# rcmix_v1.net
KiCad netlist of a schematic drawn in EAGLE
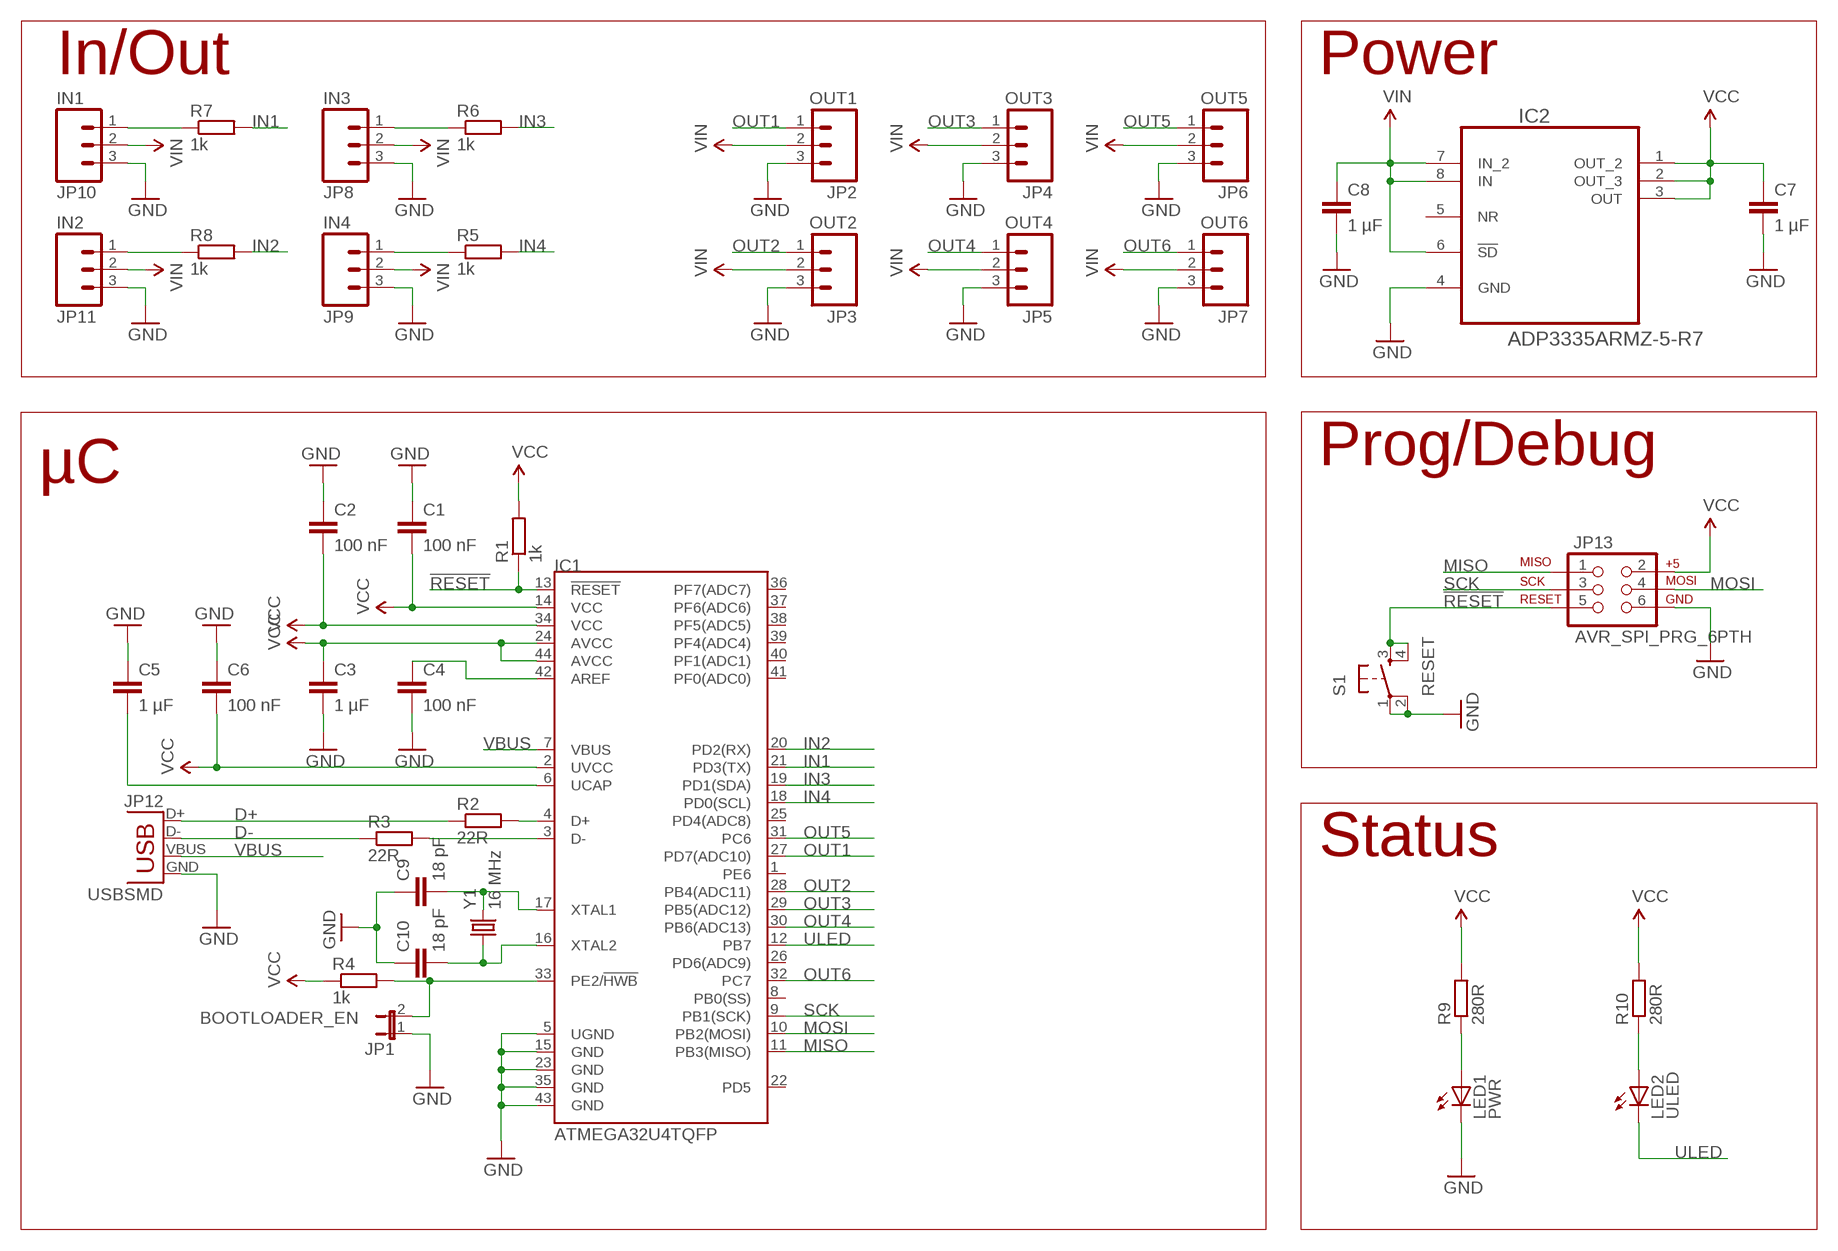
[diagram p0: schematic, sheet 1]

(export (version "E")
  (design (tool "Eeschema 10.0.6"))
  (components
    (comp (ref "C1")
      (value "100 nF")
      (footprint "eagle-import:C0603K")
      (libsource (lib "eagle-import") (part "C-EUC0603K"))
    )
    (comp (ref "C2")
      (value "100 nF")
      (footprint "eagle-import:C0603K")
      (libsource (lib "eagle-import") (part "C-EUC0603K"))
    )
    (comp (ref "C3")
      (value "1 µF")
      (footprint "eagle-import:C0603K")
      (libsource (lib "eagle-import") (part "C-EUC0603K"))
    )
    (comp (ref "C4")
      (value "100 nF")
      (footprint "eagle-import:C0603K")
      (libsource (lib "eagle-import") (part "C-EUC0603K"))
    )
    (comp (ref "C5")
      (value "1 µF")
      (footprint "eagle-import:C0603K")
      (libsource (lib "eagle-import") (part "C-EUC0603K"))
    )
    (comp (ref "C6")
      (value "100 nF")
      (footprint "eagle-import:C0603K")
      (libsource (lib "eagle-import") (part "C-EUC0603K"))
    )
    (comp (ref "C7")
      (value "1 µF")
      (footprint "eagle-import:C0603K")
      (libsource (lib "eagle-import") (part "C-EUC0603K"))
    )
    (comp (ref "C8")
      (value "1 µF")
      (footprint "eagle-import:C0603K")
      (libsource (lib "eagle-import") (part "C-EUC0603K"))
    )
    (comp (ref "C9")
      (value "18 pF")
      (footprint "eagle-import:C0603K")
      (libsource (lib "eagle-import") (part "C-EUC0603K"))
    )
    (comp (ref "C10")
      (value "18 pF")
      (footprint "eagle-import:C0603K")
      (libsource (lib "eagle-import") (part "C-EUC0603K"))
    )
    (comp (ref "IC1")
      (value "ATMEGA32U4TQFP")
      (footprint "eagle-import:SPARKFUN-DIGITALIC_TQFP44")
      (libsource (lib "eagle-import") (part "ATMEGA32U4TQFP"))
    )
    (comp (ref "IC2")
      (value "ADP3335ARMZ-5-R7")
      (footprint "eagle-import:SOP65P490X110-8N")
      (libsource (lib "eagle-import") (part "ADP3335ARMZ-5-R7"))
    )
    (comp (ref "JP1")
      (value "BOOTLOADER_EN")
      (footprint "eagle-import:JP1")
      (libsource (lib "eagle-import") (part "JP1E"))
    )
    (comp (ref "JP2")
      (value "OUT1")
      (footprint "eagle-import:1X03")
      (libsource (lib "eagle-import") (part "M03PTH"))
    )
    (comp (ref "JP3")
      (value "OUT2")
      (footprint "eagle-import:1X03")
      (libsource (lib "eagle-import") (part "M03PTH"))
    )
    (comp (ref "JP4")
      (value "OUT3")
      (footprint "eagle-import:1X03")
      (libsource (lib "eagle-import") (part "M03PTH"))
    )
    (comp (ref "JP5")
      (value "OUT4")
      (footprint "eagle-import:1X03")
      (libsource (lib "eagle-import") (part "M03PTH"))
    )
    (comp (ref "JP6")
      (value "OUT5")
      (footprint "eagle-import:1X03")
      (libsource (lib "eagle-import") (part "M03PTH"))
    )
    (comp (ref "JP7")
      (value "OUT6")
      (footprint "eagle-import:1X03")
      (libsource (lib "eagle-import") (part "M03PTH"))
    )
    (comp (ref "JP8")
      (value "IN3")
      (footprint "eagle-import:1X03")
      (libsource (lib "eagle-import") (part "M03PTH"))
    )
    (comp (ref "JP9")
      (value "IN4")
      (footprint "eagle-import:1X03")
      (libsource (lib "eagle-import") (part "M03PTH"))
    )
    (comp (ref "JP10")
      (value "IN1")
      (footprint "eagle-import:1X03")
      (libsource (lib "eagle-import") (part "M03PTH"))
    )
    (comp (ref "JP11")
      (value "IN2")
      (footprint "eagle-import:1X03")
      (libsource (lib "eagle-import") (part "M03PTH"))
    )
    (comp (ref "JP12")
      (value "USBSMD")
      (footprint "eagle-import:USB-MINIB")
      (libsource (lib "eagle-import") (part "USBSMD"))
    )
    (comp (ref "JP13")
      (value "AVR_SPI_PRG_6PTH")
      (footprint "eagle-import:2X3")
      (libsource (lib "eagle-import") (part "AVR_SPI_PRG_6PTH"))
    )
    (comp (ref "LED1")
      (value "PWR")
      (footprint "eagle-import:CHIP-LED0603")
      (libsource (lib "eagle-import") (part "LEDCHIP-LED0603"))
    )
    (comp (ref "LED2")
      (value "ULED")
      (footprint "eagle-import:CHIP-LED0603")
      (libsource (lib "eagle-import") (part "LEDCHIP-LED0603"))
    )
    (comp (ref "R1")
      (value "1k")
      (footprint "eagle-import:R0603")
      (libsource (lib "eagle-import") (part "R-EU_R0603"))
    )
    (comp (ref "R2")
      (value "22R")
      (footprint "eagle-import:R0603")
      (libsource (lib "eagle-import") (part "R-EU_R0603"))
    )
    (comp (ref "R3")
      (value "22R")
      (footprint "eagle-import:R0603")
      (libsource (lib "eagle-import") (part "R-EU_R0603"))
    )
    (comp (ref "R4")
      (value "1k")
      (footprint "eagle-import:R0603")
      (libsource (lib "eagle-import") (part "R-EU_R0603"))
    )
    (comp (ref "R5")
      (value "1k")
      (footprint "eagle-import:R0603")
      (libsource (lib "eagle-import") (part "R-EU_R0603"))
    )
    (comp (ref "R6")
      (value "1k")
      (footprint "eagle-import:R0603")
      (libsource (lib "eagle-import") (part "R-EU_R0603"))
    )
    (comp (ref "R7")
      (value "1k")
      (footprint "eagle-import:R0603")
      (libsource (lib "eagle-import") (part "R-EU_R0603"))
    )
    (comp (ref "R8")
      (value "1k")
      (footprint "eagle-import:R0603")
      (libsource (lib "eagle-import") (part "R-EU_R0603"))
    )
    (comp (ref "R9")
      (value "280R")
      (footprint "eagle-import:R0603")
      (libsource (lib "eagle-import") (part "R-EU_R0603"))
    )
    (comp (ref "R10")
      (value "280R")
      (footprint "eagle-import:R0603")
      (libsource (lib "eagle-import") (part "R-EU_R0603"))
    )
    (comp (ref "S1")
      (value "RESET")
      (footprint "eagle-import:TACTILE-PTH")
      (libsource (lib "eagle-import") (part "TAC_SWITCHPTH"))
    )
    (comp (ref "Y1")
      (value "16 MHz")
      (footprint "eagle-import:CRYSTAL-TXC-7A")
      (libsource (lib "eagle-import") (part "CRYSTALTXC-7A"))
    )
  )
  (nets
    (net (code "1") (name "/D+") (class "Default")
      (node (ref "JP12") (pin "D+") (pinfunction "D+_D+") (pintype "bidirectional"))
      (node (ref "R2") (pin "1") (pinfunction "1_1") (pintype "passive"))
    )
    (net (code "2") (name "/D-") (class "Default")
      (node (ref "JP12") (pin "D-") (pinfunction "D-_D-") (pintype "bidirectional"))
      (node (ref "R3") (pin "1") (pinfunction "1_1") (pintype "passive"))
    )
    (net (code "3") (name "/IN1") (class "Default")
      (node (ref "IC1") (pin "21") (pinfunction "PD3(TX)_21") (pintype "bidirectional"))
      (node (ref "R7") (pin "2") (pinfunction "2_2") (pintype "passive"))
    )
    (net (code "4") (name "/IN2") (class "Default")
      (node (ref "IC1") (pin "20") (pinfunction "PD2(RX)_20") (pintype "bidirectional"))
      (node (ref "R8") (pin "2") (pinfunction "2_2") (pintype "passive"))
    )
    (net (code "5") (name "/IN3") (class "Default")
      (node (ref "IC1") (pin "19") (pinfunction "PD1(SDA)_19") (pintype "bidirectional"))
      (node (ref "R6") (pin "2") (pinfunction "2_2") (pintype "passive"))
    )
    (net (code "6") (name "/IN4") (class "Default")
      (node (ref "IC1") (pin "18") (pinfunction "PD0(SCL)_18") (pintype "bidirectional"))
      (node (ref "R5") (pin "2") (pinfunction "2_2") (pintype "passive"))
    )
    (net (code "7") (name "/MISO") (class "Default")
      (node (ref "IC1") (pin "11") (pinfunction "PB3(MISO)_11") (pintype "bidirectional"))
      (node (ref "JP13") (pin "1") (pinfunction "1_1") (pintype "passive"))
    )
    (net (code "8") (name "/MOSI") (class "Default")
      (node (ref "IC1") (pin "10") (pinfunction "PB2(MOSI)_10") (pintype "bidirectional"))
      (node (ref "JP13") (pin "4") (pinfunction "4_4") (pintype "passive"))
    )
    (net (code "9") (name "/OUT1") (class "Default")
      (node (ref "IC1") (pin "27") (pinfunction "PD7(ADC10)_27") (pintype "bidirectional"))
      (node (ref "JP2") (pin "1") (pinfunction "1_1") (pintype "passive"))
    )
    (net (code "10") (name "/OUT2") (class "Default")
      (node (ref "IC1") (pin "28") (pinfunction "PB4(ADC11)_28") (pintype "bidirectional"))
      (node (ref "JP3") (pin "1") (pinfunction "1_1") (pintype "passive"))
    )
    (net (code "11") (name "/OUT3") (class "Default")
      (node (ref "IC1") (pin "29") (pinfunction "PB5(ADC12)_29") (pintype "bidirectional"))
      (node (ref "JP4") (pin "1") (pinfunction "1_1") (pintype "passive"))
    )
    (net (code "12") (name "/OUT4") (class "Default")
      (node (ref "IC1") (pin "30") (pinfunction "PB6(ADC13)_30") (pintype "bidirectional"))
      (node (ref "JP5") (pin "1") (pinfunction "1_1") (pintype "passive"))
    )
    (net (code "13") (name "/OUT5") (class "Default")
      (node (ref "IC1") (pin "31") (pinfunction "PC6_31") (pintype "bidirectional"))
      (node (ref "JP6") (pin "1") (pinfunction "1_1") (pintype "passive"))
    )
    (net (code "14") (name "/OUT6") (class "Default")
      (node (ref "IC1") (pin "32") (pinfunction "PC7_32") (pintype "bidirectional"))
      (node (ref "JP7") (pin "1") (pinfunction "1_1") (pintype "passive"))
    )
    (net (code "15") (name "/SCK") (class "Default")
      (node (ref "IC1") (pin "9") (pinfunction "PB1(SCK)_9") (pintype "bidirectional"))
      (node (ref "JP13") (pin "3") (pinfunction "3_3") (pintype "passive"))
    )
    (net (code "16") (name "/ULED") (class "Default")
      (node (ref "IC1") (pin "12") (pinfunction "PB7_12") (pintype "bidirectional"))
      (node (ref "LED2") (pin "C") (pinfunction "C_C") (pintype "passive"))
    )
    (net (code "17") (name "/VBUS") (class "Default")
      (node (ref "IC1") (pin "7") (pinfunction "VBUS_7") (pintype "bidirectional"))
      (node (ref "JP12") (pin "VBUS") (pinfunction "VBUS_VBUS") (pintype "bidirectional"))
    )
    (net (code "18") (name "/~{RESET}") (class "Default")
      (node (ref "IC1") (pin "13") (pinfunction "~{RESET}_13") (pintype "bidirectional"))
      (node (ref "JP13") (pin "5") (pinfunction "5_5") (pintype "passive"))
      (node (ref "R1") (pin "1") (pinfunction "1_1") (pintype "passive"))
      (node (ref "S1") (pin "3") (pinfunction "3_3") (pintype "passive"))
      (node (ref "S1") (pin "4") (pinfunction "4_4") (pintype "passive"))
    )
    (net (code "19") (name "GND") (class "Default")
      (node (ref "C1") (pin "1") (pinfunction "1_1") (pintype "passive"))
      (node (ref "C10") (pin "1") (pinfunction "1_1") (pintype "passive"))
      (node (ref "C2") (pin "1") (pinfunction "1_1") (pintype "passive"))
      (node (ref "C3") (pin "2") (pinfunction "2_2") (pintype "passive"))
      (node (ref "C4") (pin "2") (pinfunction "2_2") (pintype "passive"))
      (node (ref "C5") (pin "1") (pinfunction "1_1") (pintype "passive"))
      (node (ref "C6") (pin "1") (pinfunction "1_1") (pintype "passive"))
      (node (ref "C7") (pin "2") (pinfunction "2_2") (pintype "passive"))
      (node (ref "C8") (pin "2") (pinfunction "2_2") (pintype "passive"))
      (node (ref "C9") (pin "1") (pinfunction "1_1") (pintype "passive"))
      (node (ref "IC1") (pin "15") (pinfunction "GND_15") (pintype "bidirectional"))
      (node (ref "IC1") (pin "23") (pinfunction "GND_23") (pintype "bidirectional"))
      (node (ref "IC1") (pin "35") (pinfunction "GND_35") (pintype "bidirectional"))
      (node (ref "IC1") (pin "43") (pinfunction "GND_43") (pintype "bidirectional"))
      (node (ref "IC1") (pin "5") (pinfunction "UGND_5") (pintype "bidirectional"))
      (node (ref "IC2") (pin "4") (pinfunction "GND_4") (pintype "passive"))
      (node (ref "JP1") (pin "1") (pinfunction "1_1") (pintype "passive"))
      (node (ref "JP10") (pin "3") (pinfunction "3_3") (pintype "passive"))
      (node (ref "JP11") (pin "3") (pinfunction "3_3") (pintype "passive"))
      (node (ref "JP12") (pin "GND") (pinfunction "GND_GND") (pintype "bidirectional"))
      (node (ref "JP13") (pin "6") (pinfunction "6_6") (pintype "passive"))
      (node (ref "JP2") (pin "3") (pinfunction "3_3") (pintype "passive"))
      (node (ref "JP3") (pin "3") (pinfunction "3_3") (pintype "passive"))
      (node (ref "JP4") (pin "3") (pinfunction "3_3") (pintype "passive"))
      (node (ref "JP5") (pin "3") (pinfunction "3_3") (pintype "passive"))
      (node (ref "JP6") (pin "3") (pinfunction "3_3") (pintype "passive"))
      (node (ref "JP7") (pin "3") (pinfunction "3_3") (pintype "passive"))
      (node (ref "JP8") (pin "3") (pinfunction "3_3") (pintype "passive"))
      (node (ref "JP9") (pin "3") (pinfunction "3_3") (pintype "passive"))
      (node (ref "LED1") (pin "C") (pinfunction "C_C") (pintype "passive"))
      (node (ref "S1") (pin "1") (pinfunction "1_1") (pintype "passive"))
      (node (ref "S1") (pin "2") (pinfunction "2_2") (pintype "passive"))
    )
    (net (code "20") (name "Net-(IC1-AREF)") (class "Default")
      (node (ref "C4") (pin "1") (pinfunction "1_1") (pintype "passive"))
      (node (ref "IC1") (pin "42") (pinfunction "AREF_42") (pintype "bidirectional"))
    )
    (net (code "21") (name "Net-(IC1-D+)") (class "Default")
      (node (ref "IC1") (pin "4") (pinfunction "D+_4") (pintype "bidirectional"))
      (node (ref "R2") (pin "2") (pinfunction "2_2") (pintype "passive"))
    )
    (net (code "22") (name "Net-(IC1-D-)") (class "Default")
      (node (ref "IC1") (pin "3") (pinfunction "D-_3") (pintype "bidirectional"))
      (node (ref "R3") (pin "2") (pinfunction "2_2") (pintype "passive"))
    )
    (net (code "23") (name "Net-(IC1-PE2{slash}~{HWB})") (class "Default")
      (node (ref "IC1") (pin "33") (pinfunction "PE2/~{HWB}_33") (pintype "bidirectional"))
      (node (ref "JP1") (pin "2") (pinfunction "2_2") (pintype "passive"))
      (node (ref "R4") (pin "2") (pinfunction "2_2") (pintype "passive"))
    )
    (net (code "24") (name "Net-(IC1-UCAP)") (class "Default")
      (node (ref "C5") (pin "2") (pinfunction "2_2") (pintype "passive"))
      (node (ref "IC1") (pin "6") (pinfunction "UCAP_6") (pintype "bidirectional"))
    )
    (net (code "25") (name "Net-(IC1-XTAL1)") (class "Default")
      (node (ref "C9") (pin "2") (pinfunction "2_2") (pintype "passive"))
      (node (ref "IC1") (pin "17") (pinfunction "XTAL1_17") (pintype "bidirectional"))
      (node (ref "Y1") (pin "P$2") (pinfunction "2_P$2") (pintype "passive"))
    )
    (net (code "26") (name "Net-(IC1-XTAL2)") (class "Default")
      (node (ref "C10") (pin "2") (pinfunction "2_2") (pintype "passive"))
      (node (ref "IC1") (pin "16") (pinfunction "XTAL2_16") (pintype "bidirectional"))
      (node (ref "Y1") (pin "P$1") (pinfunction "1_P$1") (pintype "passive"))
    )
    (net (code "27") (name "Net-(JP8-Pad1)") (class "Default")
      (node (ref "JP8") (pin "1") (pinfunction "1_1") (pintype "passive"))
      (node (ref "R6") (pin "1") (pinfunction "1_1") (pintype "passive"))
    )
    (net (code "28") (name "Net-(JP9-Pad1)") (class "Default")
      (node (ref "JP9") (pin "1") (pinfunction "1_1") (pintype "passive"))
      (node (ref "R5") (pin "1") (pinfunction "1_1") (pintype "passive"))
    )
    (net (code "29") (name "Net-(JP10-Pad1)") (class "Default")
      (node (ref "JP10") (pin "1") (pinfunction "1_1") (pintype "passive"))
      (node (ref "R7") (pin "1") (pinfunction "1_1") (pintype "passive"))
    )
    (net (code "30") (name "Net-(JP11-Pad1)") (class "Default")
      (node (ref "JP11") (pin "1") (pinfunction "1_1") (pintype "passive"))
      (node (ref "R8") (pin "1") (pinfunction "1_1") (pintype "passive"))
    )
    (net (code "31") (name "Net-(LED1-PadA)") (class "Default")
      (node (ref "LED1") (pin "A") (pinfunction "A_A") (pintype "passive"))
      (node (ref "R9") (pin "1") (pinfunction "1_1") (pintype "passive"))
    )
    (net (code "32") (name "Net-(LED2-PadA)") (class "Default")
      (node (ref "LED2") (pin "A") (pinfunction "A_A") (pintype "passive"))
      (node (ref "R10") (pin "1") (pinfunction "1_1") (pintype "passive"))
    )
    (net (code "33") (name "VCC") (class "Default")
      (node (ref "C1") (pin "2") (pinfunction "2_2") (pintype "passive"))
      (node (ref "C2") (pin "2") (pinfunction "2_2") (pintype "passive"))
      (node (ref "C3") (pin "1") (pinfunction "1_1") (pintype "passive"))
      (node (ref "C6") (pin "2") (pinfunction "2_2") (pintype "passive"))
      (node (ref "C7") (pin "1") (pinfunction "1_1") (pintype "passive"))
      (node (ref "IC1") (pin "14") (pinfunction "VCC_14") (pintype "bidirectional"))
      (node (ref "IC1") (pin "2") (pinfunction "UVCC_2") (pintype "bidirectional"))
      (node (ref "IC1") (pin "24") (pinfunction "AVCC_24") (pintype "bidirectional"))
      (node (ref "IC1") (pin "34") (pinfunction "VCC_34") (pintype "bidirectional"))
      (node (ref "IC1") (pin "44") (pinfunction "AVCC_44") (pintype "bidirectional"))
      (node (ref "IC2") (pin "1") (pinfunction "OUT_2_1") (pintype "output"))
      (node (ref "IC2") (pin "2") (pinfunction "OUT_3_2") (pintype "output"))
      (node (ref "IC2") (pin "3") (pinfunction "OUT_3") (pintype "output"))
      (node (ref "JP13") (pin "2") (pinfunction "2_2") (pintype "passive"))
      (node (ref "R1") (pin "2") (pinfunction "2_2") (pintype "passive"))
      (node (ref "R10") (pin "2") (pinfunction "2_2") (pintype "passive"))
      (node (ref "R4") (pin "1") (pinfunction "1_1") (pintype "passive"))
      (node (ref "R9") (pin "2") (pinfunction "2_2") (pintype "passive"))
    )
    (net (code "34") (name "VIN") (class "Default")
      (node (ref "C8") (pin "1") (pinfunction "1_1") (pintype "passive"))
      (node (ref "IC2") (pin "6") (pinfunction "~{SD}_6") (pintype "input"))
      (node (ref "IC2") (pin "7") (pinfunction "IN_2_7") (pintype "input"))
      (node (ref "IC2") (pin "8") (pinfunction "IN_8") (pintype "input"))
      (node (ref "JP10") (pin "2") (pinfunction "2_2") (pintype "passive"))
      (node (ref "JP11") (pin "2") (pinfunction "2_2") (pintype "passive"))
      (node (ref "JP2") (pin "2") (pinfunction "2_2") (pintype "passive"))
      (node (ref "JP3") (pin "2") (pinfunction "2_2") (pintype "passive"))
      (node (ref "JP4") (pin "2") (pinfunction "2_2") (pintype "passive"))
      (node (ref "JP5") (pin "2") (pinfunction "2_2") (pintype "passive"))
      (node (ref "JP6") (pin "2") (pinfunction "2_2") (pintype "passive"))
      (node (ref "JP7") (pin "2") (pinfunction "2_2") (pintype "passive"))
      (node (ref "JP8") (pin "2") (pinfunction "2_2") (pintype "passive"))
      (node (ref "JP9") (pin "2") (pinfunction "2_2") (pintype "passive"))
    )
    (net (code "35") (name "unconnected-(IC1-PB0(SS)-Pad8)") (class "Default")
      (node (ref "IC1") (pin "8") (pinfunction "PB0(SS)_8") (pintype "bidirectional"))
    )
    (net (code "36") (name "unconnected-(IC1-PD4(ADC8)-Pad25)") (class "Default")
      (node (ref "IC1") (pin "25") (pinfunction "PD4(ADC8)_25") (pintype "bidirectional"))
    )
    (net (code "37") (name "unconnected-(IC1-PD5-Pad22)") (class "Default")
      (node (ref "IC1") (pin "22") (pinfunction "PD5_22") (pintype "bidirectional"))
    )
    (net (code "38") (name "unconnected-(IC1-PD6(ADC9)-Pad26)") (class "Default")
      (node (ref "IC1") (pin "26") (pinfunction "PD6(ADC9)_26") (pintype "bidirectional"))
    )
    (net (code "39") (name "unconnected-(IC1-PE6-Pad1)") (class "Default")
      (node (ref "IC1") (pin "1") (pinfunction "PE6_1") (pintype "bidirectional"))
    )
    (net (code "40") (name "unconnected-(IC1-PF0(ADC0)-Pad41)") (class "Default")
      (node (ref "IC1") (pin "41") (pinfunction "PF0(ADC0)_41") (pintype "bidirectional"))
    )
    (net (code "41") (name "unconnected-(IC1-PF1(ADC1)-Pad40)") (class "Default")
      (node (ref "IC1") (pin "40") (pinfunction "PF1(ADC1)_40") (pintype "bidirectional"))
    )
    (net (code "42") (name "unconnected-(IC1-PF4(ADC4)-Pad39)") (class "Default")
      (node (ref "IC1") (pin "39") (pinfunction "PF4(ADC4)_39") (pintype "bidirectional"))
    )
    (net (code "43") (name "unconnected-(IC1-PF5(ADC5)-Pad38)") (class "Default")
      (node (ref "IC1") (pin "38") (pinfunction "PF5(ADC5)_38") (pintype "bidirectional"))
    )
    (net (code "44") (name "unconnected-(IC1-PF6(ADC6)-Pad37)") (class "Default")
      (node (ref "IC1") (pin "37") (pinfunction "PF6(ADC6)_37") (pintype "bidirectional"))
    )
    (net (code "45") (name "unconnected-(IC1-PF7(ADC7)-Pad36)") (class "Default")
      (node (ref "IC1") (pin "36") (pinfunction "PF7(ADC7)_36") (pintype "bidirectional"))
    )
    (net (code "46") (name "unconnected-(IC2-NR-Pad5)") (class "Default")
      (node (ref "IC2") (pin "5") (pinfunction "NR_5") (pintype "input"))
    )
  )
)
